# PWMController.net
KiCad netlist of a schematic drawn in Altium Designer
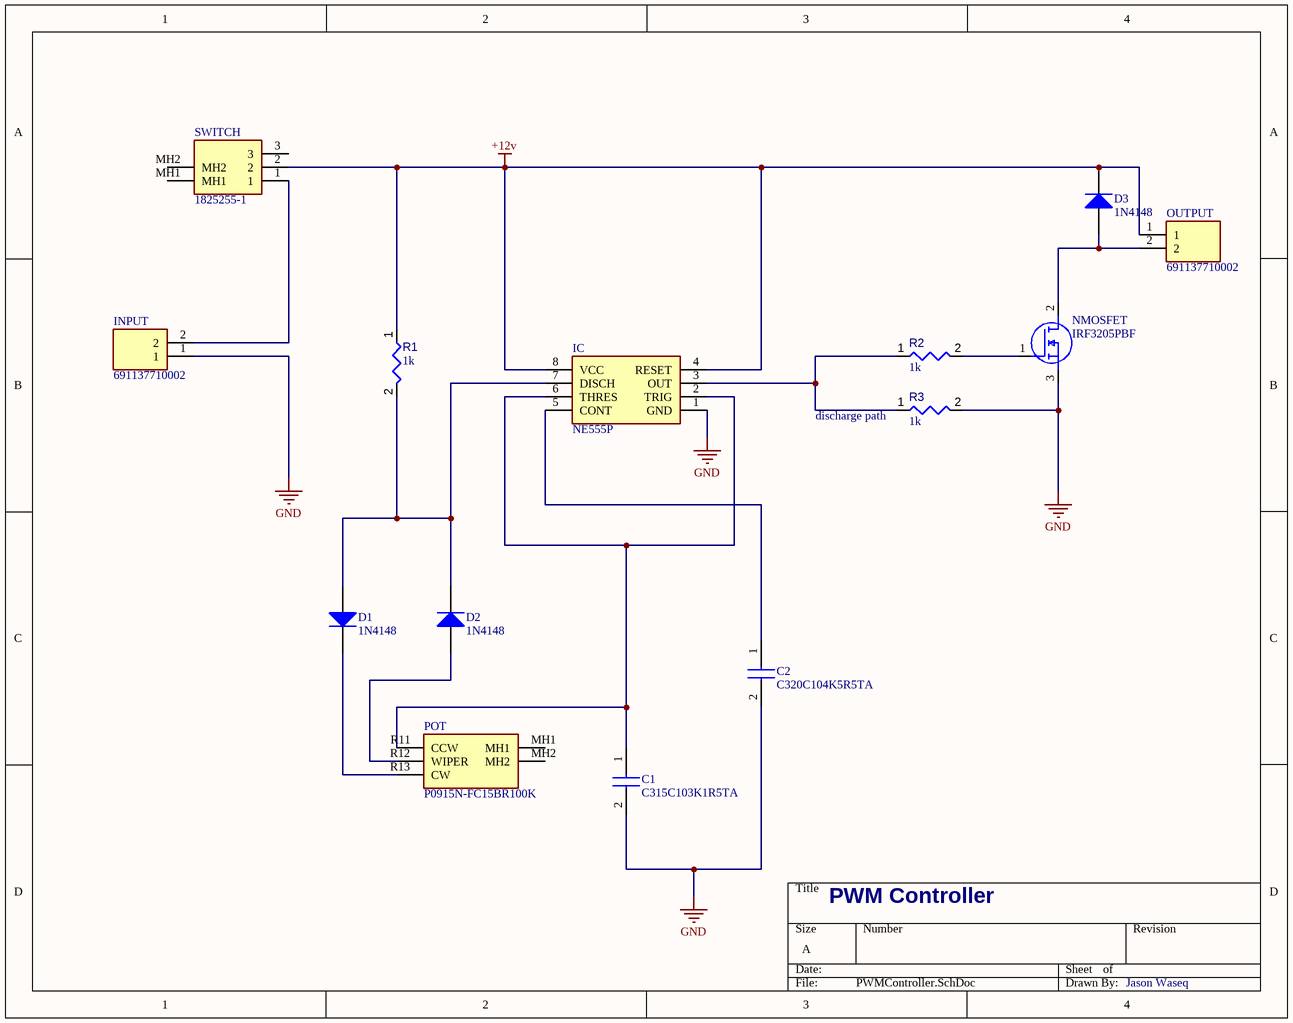
[diagram p0: PWMController.SchDoc]

(export (version "E")
  (design (tool "Eeschema 10.0.6"))
  (components
    (comp (ref "C1")
      (value "C315C103K1R5TA")
      (footprint "SamacSys:C315C103K1R5TA")
      (description "Capacitor")
      (fields (field (name "MOUSER PART NUMBER") "80-C315C103K1R"))
      (libsource (lib "*") (part "C315C103K1R5TA"))
    )
    (comp (ref "C2")
      (value "C320C104K5R5TA")
      (footprint "SamacSys:C320C104K5R5TA")
      (description "Capacitor")
      (fields (field (name "MOUSER PART NUMBER") "80-C320C104K5R"))
      (libsource (lib "*") (part "C320C104K5R5TA"))
    )
    (comp (ref "D1")
      (value "1N4148")
      (footprint "NXP-SOD27-2_V")
      (description "High Speed Diode, 100 V, 0.45 A, -65 to 175 degC, 2-Pin SOD27, RoHS, Bulk")
      (fields (field (name "POWER") "500mW") (field (name "MANUFACTURER") "Fairchild"))
      (libsource (lib "Jason Waseq Altium Workspace") (part "D-AK-2"))
    )
    (comp (ref "D2")
      (value "1N4148")
      (footprint "NXP-SOD27-2_V")
      (description "High Speed Diode, 100 V, 0.45 A, -65 to 175 degC, 2-Pin SOD27, RoHS, Bulk")
      (fields (field (name "POWER") "500mW") (field (name "MANUFACTURER") "Fairchild"))
      (libsource (lib "Jason Waseq Altium Workspace") (part "D-AK-2"))
    )
    (comp (ref "D3")
      (value "1N4148")
      (footprint "NXP-SOD27-2_V")
      (description "High Speed Diode, 100 V, 0.45 A, -65 to 175 degC, 2-Pin SOD27, RoHS, Bulk")
      (fields (field (name "POWER") "500mW") (field (name "MANUFACTURER") "Fairchild"))
      (libsource (lib "Jason Waseq Altium Workspace") (part "D-AK-2"))
    )
    (comp (ref "IC")
      (value "NE555P")
      (footprint "SamacSys:DIP794W53P254L959H508Q8N")
      (description "Integrated Circuit")
      (fields (field (name "MOUSER PART NUMBER") "595-NE555P"))
      (libsource (lib "*") (part "NE555P"))
    )
    (comp (ref "INPUT")
      (value "691137710002")
      (footprint "SamacSys:SHDR2W70P0X500_1X2_1000X750X1160P")
      (description "Connector")
      (fields (field (name "MOUSER PART NUMBER") "710-691137710002"))
      (libsource (lib "*") (part "691137710002"))
    )
    (comp (ref "NMOSFET")
      (value "IRF3205PBF")
      (footprint "SamacSys:TO254P483X1016X1994-3P")
      (description "MOSFET (N-Channel)")
      (fields (field (name "MOUSER PART NUMBER") "942-IRF3205PBF"))
      (libsource (lib "*") (part "IRF3205PBF"))
    )
    (comp (ref "OUTPUT")
      (value "691137710002")
      (footprint "SamacSys:SHDR2W70P0X500_1X2_1000X750X1160P")
      (description "Connector")
      (fields (field (name "MOUSER PART NUMBER") "710-691137710002"))
      (libsource (lib "") (part "691137710002_1"))
    )
    (comp (ref "POT")
      (value "P0915N-FC15BR100K")
      (footprint "SamacSys:P0915NFC15BR100K")
      (description "Variable Resistor")
      (fields (field (name "MOUSER PART NUMBER") "858-P0915NFC15BR100K"))
      (libsource (lib "*") (part "P0915N-FC15BR100K"))
    )
    (comp (ref "R1")
      (value "1k")
      (footprint "RESA60-630X240")
      (description "Axial Resistor, 1 KOhm, +/- 1%, 250 mW, -55 to 155 degC, 2-Pin THD, RoHS, Bulk")
      (fields (field (name "TOLERANCE") "1%") (field (name "POWER") "250mW"))
      (libsource (lib "Jason Waseq Altium Workspace") (part "RES-2"))
    )
    (comp (ref "R2")
      (value "1k")
      (footprint "RESA60-630X240")
      (description "Axial Resistor, 1 KOhm, +/- 1%, 250 mW, -55 to 155 degC, 2-Pin THD, RoHS, Bulk")
      (fields (field (name "TOLERANCE") "1%") (field (name "POWER") "250mW"))
      (libsource (lib "Jason Waseq Altium Workspace") (part "RES-2"))
    )
    (comp (ref "R3")
      (value "1k")
      (footprint "RESA60-630X240")
      (description "Axial Resistor, 1 KOhm, +/- 1%, 250 mW, -55 to 155 degC, 2-Pin THD, RoHS, Bulk")
      (fields (field (name "TOLERANCE") "1%") (field (name "POWER") "250mW"))
      (libsource (lib "Jason Waseq Altium Workspace") (part "RES-2"))
    )
    (comp (ref "SWITCH")
      (value "1825255-1")
      (footprint "SamacSys:18252551")
      (description "Switch")
      (libsource (lib "*") (part "1825255-1"))
    )
  )
  (nets
    (net (code "1") (name "+12v") (class "Default")
      (node (ref "D3") (pin "2") (pinfunction "K_2") (pintype "passive"))
      (node (ref "IC") (pin "4") (pinfunction "RESET_4") (pintype "passive"))
      (node (ref "IC") (pin "8") (pinfunction "VCC_8") (pintype "passive"))
      (node (ref "OUTPUT") (pin "1") (pinfunction "1_1") (pintype "passive"))
      (node (ref "R1") (pin "1") (pinfunction "1_1") (pintype "passive"))
      (node (ref "SWITCH") (pin "2") (pinfunction "2_2") (pintype "passive"))
    )
    (net (code "2") (name "GND") (class "Default")
      (node (ref "C1") (pin "2") (pinfunction "2_2") (pintype "passive"))
      (node (ref "C2") (pin "2") (pinfunction "2_2") (pintype "passive"))
      (node (ref "IC") (pin "1") (pinfunction "GND_1") (pintype "passive"))
      (node (ref "INPUT") (pin "1") (pinfunction "1_1") (pintype "passive"))
      (node (ref "NMOSFET") (pin "3") (pinfunction "S_3") (pintype "passive"))
      (node (ref "R3") (pin "2") (pinfunction "2_2") (pintype "passive"))
    )
    (net (code "3") (name "Net-(D1-A)") (class "Default")
      (node (ref "D1") (pin "1") (pinfunction "A_1") (pintype "passive"))
      (node (ref "D2") (pin "2") (pinfunction "K_2") (pintype "passive"))
      (node (ref "IC") (pin "7") (pinfunction "DISCH_7") (pintype "passive"))
      (node (ref "R1") (pin "2") (pinfunction "2_2") (pintype "passive"))
    )
    (net (code "4") (name "Net-(D1-K)") (class "Default")
      (node (ref "D1") (pin "2") (pinfunction "K_2") (pintype "passive"))
      (node (ref "POT") (pin "R13") (pinfunction "CW_R13") (pintype "passive"))
    )
    (net (code "5") (name "Net-(D2-A)") (class "Default")
      (node (ref "D2") (pin "1") (pinfunction "A_1") (pintype "passive"))
      (node (ref "POT") (pin "R12") (pinfunction "WIPER_R12") (pintype "passive"))
    )
    (net (code "6") (name "Net-(D3-A)") (class "Default")
      (node (ref "D3") (pin "1") (pinfunction "A_1") (pintype "passive"))
      (node (ref "NMOSFET") (pin "2") (pinfunction "D_2") (pintype "passive"))
      (node (ref "OUTPUT") (pin "2") (pinfunction "2_2") (pintype "passive"))
    )
    (net (code "7") (name "Net-(IC-CONT)") (class "Default")
      (node (ref "C2") (pin "1") (pinfunction "1_1") (pintype "passive"))
      (node (ref "IC") (pin "5") (pinfunction "CONT_5") (pintype "passive"))
    )
    (net (code "8") (name "Net-(IC-OUT)") (class "Default")
      (node (ref "IC") (pin "3") (pinfunction "OUT_3") (pintype "passive"))
      (node (ref "R2") (pin "1") (pinfunction "1_1") (pintype "passive"))
      (node (ref "R3") (pin "1") (pinfunction "1_1") (pintype "passive"))
    )
    (net (code "9") (name "Net-(IC-THRES)") (class "Default")
      (node (ref "C1") (pin "1") (pinfunction "1_1") (pintype "passive"))
      (node (ref "IC") (pin "2") (pinfunction "TRIG_2") (pintype "passive"))
      (node (ref "IC") (pin "6") (pinfunction "THRES_6") (pintype "passive"))
      (node (ref "POT") (pin "R11") (pinfunction "CCW_R11") (pintype "passive"))
    )
    (net (code "10") (name "Net-(INPUT-Pad2)") (class "Default")
      (node (ref "INPUT") (pin "2") (pinfunction "2_2") (pintype "passive"))
      (node (ref "SWITCH") (pin "1") (pinfunction "1_1") (pintype "passive"))
    )
    (net (code "11") (name "Net-(NMOSFET-G)") (class "Default")
      (node (ref "NMOSFET") (pin "1") (pinfunction "G_1") (pintype "passive"))
      (node (ref "R2") (pin "2") (pinfunction "2_2") (pintype "passive"))
    )
    (net (code "12") (name "unconnected-(POT-PadMH1)") (class "Default")
      (node (ref "POT") (pin "MH1") (pinfunction "MH1_MH1") (pintype "passive"))
    )
    (net (code "13") (name "unconnected-(POT-PadMH2)") (class "Default")
      (node (ref "POT") (pin "MH2") (pinfunction "MH2_MH2") (pintype "passive"))
    )
    (net (code "14") (name "unconnected-(SWITCH-Pad3)") (class "Default")
      (node (ref "SWITCH") (pin "3") (pinfunction "3_3") (pintype "passive"))
    )
    (net (code "15") (name "unconnected-(SWITCH-PadMH1)") (class "Default")
      (node (ref "SWITCH") (pin "MH1") (pinfunction "MH1_MH1") (pintype "passive"))
    )
    (net (code "16") (name "unconnected-(SWITCH-PadMH2)") (class "Default")
      (node (ref "SWITCH") (pin "MH2") (pinfunction "MH2_MH2") (pintype "passive"))
    )
  )
)
